# CurrentSenseAmp.net
KiCad netlist of a schematic drawn in Altium Designer
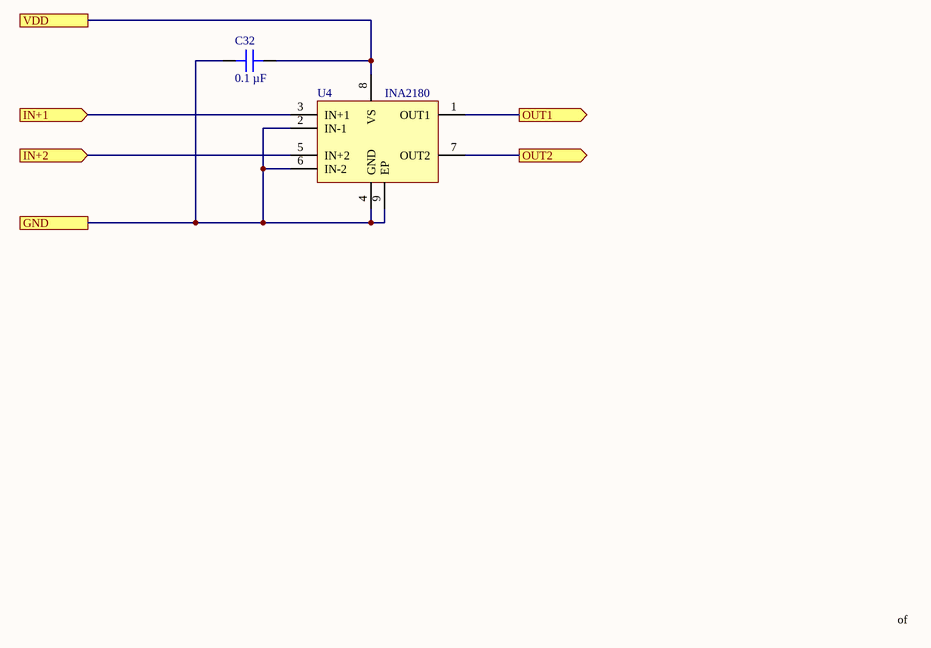
[diagram p0: CurrentSenseAmp.SchDoc]

(export (version "E")
  (design (tool "Eeschema 10.0.6"))
  (components
    (comp (ref "C32")
      (value "0.1 µF")
      (footprint "CAP 0201_0603")
      (description "CAP CER 0.1UF 35V X5R 0201")
      (fields
        (field (name "PART NUMBER") "GRT033R6YA104KE01D")
        (field (name "MANUFACTURER") "Murata Electronics")
      )
      (libsource (lib "Celestial Altium Library - altium_library") (part "Capacitor"))
    )
    (comp (ref "U4")
      (value "INA2180")
      (footprint "WSON-8_2x2")
      (description "Current sense amplifier 4 channel")
      (libsource (lib "IC") (part "INA2180"))
    )
  )
  (nets
    (net (code "1") (name "/GND") (class "Default")
      (node (ref "C32") (pin "1") (pinfunction "1_1") (pintype "passive"))
      (node (ref "U4") (pin "2") (pinfunction "IN-1_2") (pintype "passive"))
      (node (ref "U4") (pin "4") (pinfunction "GND_4") (pintype "passive"))
      (node (ref "U4") (pin "6") (pinfunction "IN-2_6") (pintype "passive"))
      (node (ref "U4") (pin "9") (pinfunction "EP_9") (pintype "passive"))
    )
    (net (code "2") (name "/IN+1") (class "Default")
      (node (ref "U4") (pin "3") (pinfunction "IN+1_3") (pintype "passive"))
    )
    (net (code "3") (name "/IN+2") (class "Default")
      (node (ref "U4") (pin "5") (pinfunction "IN+2_5") (pintype "passive"))
    )
    (net (code "4") (name "/OUT1") (class "Default")
      (node (ref "U4") (pin "1") (pinfunction "OUT1_1") (pintype "passive"))
    )
    (net (code "5") (name "/OUT2") (class "Default")
      (node (ref "U4") (pin "7") (pinfunction "OUT2_7") (pintype "passive"))
    )
    (net (code "6") (name "/VDD") (class "Default")
      (node (ref "C32") (pin "2") (pinfunction "2_2") (pintype "passive"))
      (node (ref "U4") (pin "8") (pinfunction "VS_8") (pintype "passive"))
    )
  )
)
